# c150.net
KiCad netlist of a schematic drawn in EAGLE
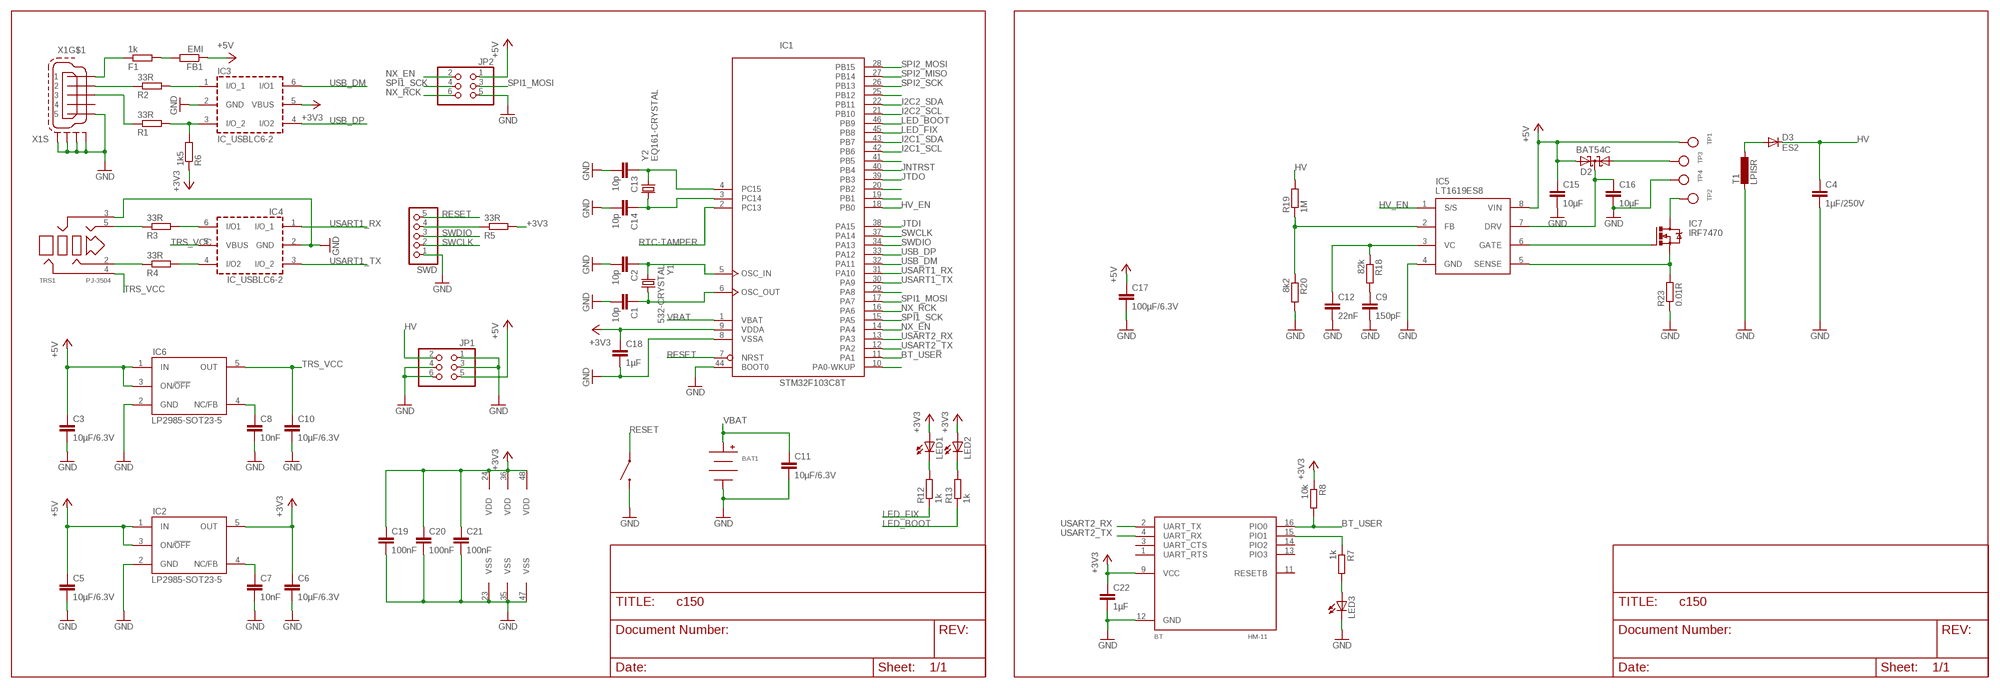
[diagram p0: schematic, sheet 1]

(export (version "E")
  (design (tool "Eeschema 10.0.6"))
  (components
    (comp (ref "BAT1")
      (value "CR1220-HOLDER")
      (footprint "eagle-import:HARWIN-CR1220")
      (libsource (lib "eagle-import") (part "CR1220-HOLDER"))
    )
    (comp (ref "BT")
      (value "HM-11")
      (footprint "eagle-import:HM-11")
      (libsource (lib "eagle-import") (part "HM-11"))
    )
    (comp (ref "C1")
      (value "10p")
      (footprint "eagle-import:C0603")
      (libsource (lib "eagle-import") (part "C-EUC0603"))
    )
    (comp (ref "C2")
      (value "10p")
      (footprint "eagle-import:C0603")
      (libsource (lib "eagle-import") (part "C-EUC0603"))
    )
    (comp (ref "C3")
      (value "10µF/6.3V")
      (footprint "eagle-import:C0603")
      (libsource (lib "eagle-import") (part "C-EUC0603"))
    )
    (comp (ref "C4")
      (value "1µF/250V")
      (footprint "eagle-import:C2220K")
      (libsource (lib "eagle-import") (part "C-EUC2220K"))
    )
    (comp (ref "C5")
      (value "10µF/6.3V")
      (footprint "eagle-import:C0603")
      (libsource (lib "eagle-import") (part "C-EUC0603"))
    )
    (comp (ref "C6")
      (value "10µF/6.3V")
      (footprint "eagle-import:C0603")
      (libsource (lib "eagle-import") (part "C-EUC0603"))
    )
    (comp (ref "C7")
      (value "10nF")
      (footprint "eagle-import:C0603")
      (libsource (lib "eagle-import") (part "C-EUC0603"))
    )
    (comp (ref "C8")
      (value "10nF")
      (footprint "eagle-import:C0603")
      (libsource (lib "eagle-import") (part "C-EUC0603"))
    )
    (comp (ref "C9")
      (value "150pF")
      (footprint "eagle-import:C0603")
      (libsource (lib "eagle-import") (part "C-EUC0603"))
    )
    (comp (ref "C10")
      (value "10µF/6.3V")
      (footprint "eagle-import:C0603")
      (libsource (lib "eagle-import") (part "C-EUC0603"))
    )
    (comp (ref "C11")
      (value "10µF/6.3V")
      (footprint "eagle-import:C0603")
      (libsource (lib "eagle-import") (part "C-EUC0603"))
    )
    (comp (ref "C12")
      (value "22nF")
      (footprint "eagle-import:C0603")
      (libsource (lib "eagle-import") (part "C-EUC0603"))
    )
    (comp (ref "C13")
      (value "10p")
      (footprint "eagle-import:C0603")
      (libsource (lib "eagle-import") (part "C-EUC0603"))
    )
    (comp (ref "C14")
      (value "10p")
      (footprint "eagle-import:C0603")
      (libsource (lib "eagle-import") (part "C-EUC0603"))
    )
    (comp (ref "C15")
      (value "10µF")
      (footprint "eagle-import:C0603")
      (libsource (lib "eagle-import") (part "C-EUC0603"))
    )
    (comp (ref "C16")
      (value "10µF")
      (footprint "eagle-import:C0603")
      (libsource (lib "eagle-import") (part "C-EUC0603"))
    )
    (comp (ref "C17")
      (value "100µF/6.3V")
      (footprint "eagle-import:C1210")
      (libsource (lib "eagle-import") (part "C-EUC1210"))
    )
    (comp (ref "C18")
      (value "1µF")
      (footprint "eagle-import:C0603")
      (libsource (lib "eagle-import") (part "C-EUC0603"))
    )
    (comp (ref "C19")
      (value "100nF")
      (footprint "eagle-import:C0603")
      (libsource (lib "eagle-import") (part "C-EUC0603"))
    )
    (comp (ref "C20")
      (value "100nF")
      (footprint "eagle-import:C0603")
      (libsource (lib "eagle-import") (part "C-EUC0603"))
    )
    (comp (ref "C21")
      (value "100nF")
      (footprint "eagle-import:C0603")
      (libsource (lib "eagle-import") (part "C-EUC0603"))
    )
    (comp (ref "C22")
      (value "1µF")
      (footprint "eagle-import:C0603")
      (libsource (lib "eagle-import") (part "C-EUC0603"))
    )
    (comp (ref "D2")
      (value "BAT54C")
      (footprint "eagle-import:SOT23")
      (libsource (lib "eagle-import") (part "BAT54C"))
    )
    (comp (ref "D3")
      (value "ES2")
      (footprint "eagle-import:DO-214AA")
      (libsource (lib "eagle-import") (part "ES2"))
    )
    (comp (ref "F1")
      (value "1k")
      (footprint "eagle-import:R0603")
      (libsource (lib "eagle-import") (part "R-EU_R0603"))
    )
    (comp (ref "FB1")
      (value "EMI")
      (footprint "eagle-import:R0603")
      (libsource (lib "eagle-import") (part "R-EU_R0603"))
    )
    (comp (ref "IC1")
      (value "STM32F103C8T")
      (footprint "eagle-import:LQFP48")
      (libsource (lib "eagle-import") (part "STM32F103CT8"))
    )
    (comp (ref "IC2")
      (value "LP2985-SOT23-5")
      (footprint "eagle-import:SOT23-5")
      (libsource (lib "eagle-import") (part "LP2985-SOT23-5"))
    )
    (comp (ref "IC3")
      (value "IC_USBLC6-2")
      (footprint "eagle-import:SOT-23-6L")
      (libsource (lib "eagle-import") (part "IC_USBLC6-2"))
    )
    (comp (ref "IC4")
      (value "IC_USBLC6-2")
      (footprint "eagle-import:SOT-23-6L")
      (libsource (lib "eagle-import") (part "IC_USBLC6-2"))
    )
    (comp (ref "IC5")
      (value "LT1619ES8")
      (footprint "eagle-import:SO8")
      (libsource (lib "eagle-import") (part "LT1619ES8"))
    )
    (comp (ref "IC6")
      (value "LP2985-SOT23-5")
      (footprint "eagle-import:SOT23-5")
      (libsource (lib "eagle-import") (part "LP2985-SOT23-5"))
    )
    (comp (ref "IC7")
      (value "IRF7470")
      (footprint "eagle-import:SO8")
      (libsource (lib "eagle-import") (part "IRF7470"))
    )
    (comp (ref "ISP")
      (value "TACT-SWITCH-40-40")
      (footprint "eagle-import:40-40")
      (libsource (lib "eagle-import") (part "TACT-SWITCH-40-40"))
    )
    (comp (ref "JP1")
      (value "PINHD-2X3_2.54-SMD")
      (footprint "eagle-import:2X03SMD")
      (libsource (lib "eagle-import") (part "PINHD-2X3_2.54-SMD"))
    )
    (comp (ref "JP2")
      (value "PINHD-2X3_2.54-SMD")
      (footprint "eagle-import:2X03SMD")
      (libsource (lib "eagle-import") (part "PINHD-2X3_2.54-SMD"))
    )
    (comp (ref "LED1")
      (value "LEDCHIP-LED0603")
      (footprint "eagle-import:CHIP-LED0603")
      (libsource (lib "eagle-import") (part "LEDCHIP-LED0603"))
    )
    (comp (ref "LED2")
      (value "LEDCHIP-LED0603")
      (footprint "eagle-import:CHIP-LED0603")
      (libsource (lib "eagle-import") (part "LEDCHIP-LED0603"))
    )
    (comp (ref "LED3")
      (value "LEDCHIP-LED0603")
      (footprint "eagle-import:CHIP-LED0603")
      (libsource (lib "eagle-import") (part "LEDCHIP-LED0603"))
    )
    (comp (ref "R1")
      (value "33R")
      (footprint "eagle-import:R0603")
      (libsource (lib "eagle-import") (part "R-EU_R0603"))
    )
    (comp (ref "R2")
      (value "33R")
      (footprint "eagle-import:R0603")
      (libsource (lib "eagle-import") (part "R-EU_R0603"))
    )
    (comp (ref "R3")
      (value "33R")
      (footprint "eagle-import:R0603")
      (libsource (lib "eagle-import") (part "R-EU_R0603"))
    )
    (comp (ref "R4")
      (value "33R")
      (footprint "eagle-import:R0603")
      (libsource (lib "eagle-import") (part "R-EU_R0603"))
    )
    (comp (ref "R5")
      (value "33R")
      (footprint "eagle-import:R0603")
      (libsource (lib "eagle-import") (part "R-EU_R0603"))
    )
    (comp (ref "R6")
      (value "1k5")
      (footprint "eagle-import:R0603")
      (libsource (lib "eagle-import") (part "R-EU_R0603"))
    )
    (comp (ref "R7")
      (value "1k")
      (footprint "eagle-import:R0603")
      (libsource (lib "eagle-import") (part "R-EU_R0603"))
    )
    (comp (ref "R8")
      (value "10k")
      (footprint "eagle-import:R0603")
      (libsource (lib "eagle-import") (part "R-EU_R0603"))
    )
    (comp (ref "R12")
      (value "1k")
      (footprint "eagle-import:R0603")
      (libsource (lib "eagle-import") (part "R-EU_R0603"))
    )
    (comp (ref "R13")
      (value "1k")
      (footprint "eagle-import:R0603")
      (libsource (lib "eagle-import") (part "R-EU_R0603"))
    )
    (comp (ref "R18")
      (value "82k")
      (footprint "eagle-import:R0603")
      (libsource (lib "eagle-import") (part "R-EU_R0603"))
    )
    (comp (ref "R19")
      (value "1M")
      (footprint "eagle-import:M1206")
      (libsource (lib "eagle-import") (part "R-EU_M1206"))
    )
    (comp (ref "R20")
      (value "8k2")
      (footprint "eagle-import:R0603")
      (libsource (lib "eagle-import") (part "R-EU_R0603"))
    )
    (comp (ref "R23")
      (value "0.01R")
      (footprint "eagle-import:R1206")
      (libsource (lib "eagle-import") (part "R-EU_R1206"))
    )
    (comp (ref "SWD")
      (value "HEADER-1X5ROUND")
      (footprint "eagle-import:1X05_ROUND")
      (libsource (lib "eagle-import") (part "HEADER-1X5ROUND"))
    )
    (comp (ref "T1")
      (value "LPISR")
      (footprint "eagle-import:PISR")
      (libsource (lib "eagle-import") (part "LPISR"))
    )
    (comp (ref "TP1")
      (value "TESTPOINTROUND2MM")
      (footprint "eagle-import:TESTPOINT_ROUND_2MM")
      (libsource (lib "eagle-import") (part "TESTPOINTROUND2MM"))
    )
    (comp (ref "TP2")
      (value "TESTPOINTROUND2MM")
      (footprint "eagle-import:TESTPOINT_ROUND_2MM")
      (libsource (lib "eagle-import") (part "TESTPOINTROUND2MM"))
    )
    (comp (ref "TP3")
      (value "TESTPOINTROUND2MM")
      (footprint "eagle-import:TESTPOINT_ROUND_2MM")
      (libsource (lib "eagle-import") (part "TESTPOINTROUND2MM"))
    )
    (comp (ref "TP4")
      (value "TESTPOINTROUND2MM")
      (footprint "eagle-import:TESTPOINT_ROUND_2MM")
      (libsource (lib "eagle-import") (part "TESTPOINTROUND2MM"))
    )
    (comp (ref "TRS1")
      (value "PJ-3504")
      (footprint "eagle-import:YD-PJ-3504")
      (libsource (lib "eagle-import") (part "PJ-3504"))
    )
    (comp (ref "X1")
      (value "MINI-USB-SCHIELD-32005-201")
      (footprint "eagle-import:32005-201")
      (libsource (lib "eagle-import") (part "MINI-USB-SCHIELD-32005-201"))
    )
    (comp (ref "Y1")
      (value "532-CRYSTAL")
      (footprint "eagle-import:2PIN50X32")
      (libsource (lib "eagle-import") (part "532-CRYSTAL"))
    )
    (comp (ref "Y2")
      (value "EQ161-CRYSTAL")
      (footprint "eagle-import:EQ161")
      (libsource (lib "eagle-import") (part "EQ161-CRYSTAL"))
    )
  )
  (nets
    (net (code "1") (name "+3V3") (class "Default")
      (node (ref "BT") (pin "9") (pinfunction "VCC_9") (pintype "bidirectional"))
      (node (ref "C18") (pin "1") (pinfunction "1_1") (pintype "passive"))
      (node (ref "C19") (pin "1") (pinfunction "1_1") (pintype "passive"))
      (node (ref "C20") (pin "1") (pinfunction "1_1") (pintype "passive"))
      (node (ref "C21") (pin "1") (pinfunction "1_1") (pintype "passive"))
      (node (ref "C22") (pin "1") (pinfunction "1_1") (pintype "passive"))
      (node (ref "C6") (pin "1") (pinfunction "1_1") (pintype "passive"))
      (node (ref "IC1") (pin "24") (pinfunction "VDD_24") (pintype "power_in"))
      (node (ref "IC1") (pin "36") (pinfunction "VDD_36") (pintype "power_in"))
      (node (ref "IC1") (pin "48") (pinfunction "VDD_48") (pintype "power_in"))
      (node (ref "IC1") (pin "9") (pinfunction "VDDA_9") (pintype "power_in"))
      (node (ref "IC2") (pin "5") (pinfunction "OUT_5") (pintype "bidirectional"))
      (node (ref "IC3") (pin "5") (pinfunction "VBUS_5") (pintype "bidirectional"))
      (node (ref "LED1") (pin "A") (pinfunction "A_A") (pintype "passive"))
      (node (ref "LED2") (pin "A") (pinfunction "A_A") (pintype "passive"))
      (node (ref "R5") (pin "2") (pinfunction "2_2") (pintype "passive"))
      (node (ref "R6") (pin "1") (pinfunction "1_1") (pintype "passive"))
      (node (ref "R8") (pin "1") (pinfunction "1_1") (pintype "passive"))
    )
    (net (code "2") (name "+5V") (class "Default")
      (node (ref "C15") (pin "1") (pinfunction "1_1") (pintype "passive"))
      (node (ref "C17") (pin "1") (pinfunction "1_1") (pintype "passive"))
      (node (ref "C3") (pin "1") (pinfunction "1_1") (pintype "passive"))
      (node (ref "C5") (pin "1") (pinfunction "1_1") (pintype "passive"))
      (node (ref "D2") (pin "2") (pinfunction "A2_2") (pintype "passive"))
      (node (ref "FB1") (pin "1") (pinfunction "1_1") (pintype "passive"))
      (node (ref "IC2") (pin "1") (pinfunction "IN_1") (pintype "bidirectional"))
      (node (ref "IC2") (pin "3") (pinfunction "ON/~{OFF}_3") (pintype "bidirectional"))
      (node (ref "IC5") (pin "8") (pinfunction "VIN_8") (pintype "bidirectional"))
      (node (ref "IC6") (pin "1") (pinfunction "IN_1") (pintype "bidirectional"))
      (node (ref "IC6") (pin "3") (pinfunction "ON/~{OFF}_3") (pintype "bidirectional"))
      (node (ref "JP1") (pin "5") (pinfunction "5_5") (pintype "passive"))
      (node (ref "JP2") (pin "1") (pinfunction "1_1") (pintype "passive"))
      (node (ref "TP1") (pin "P$1") (pinfunction "P$1_P$1") (pintype "bidirectional"))
    )
    (net (code "3") (name "/BT_USER") (class "Default")
      (node (ref "BT") (pin "16") (pinfunction "PIO0_16") (pintype "bidirectional"))
      (node (ref "IC1") (pin "11") (pinfunction "PA1_11") (pintype "bidirectional"))
      (node (ref "R8") (pin "2") (pinfunction "2_2") (pintype "passive"))
    )
    (net (code "4") (name "/HV") (class "Default")
      (node (ref "C4") (pin "1") (pinfunction "1_1") (pintype "passive"))
      (node (ref "D3") (pin "C") (pinfunction "C_C") (pintype "passive"))
      (node (ref "JP1") (pin "2") (pinfunction "2_2") (pintype "passive"))
      (node (ref "R19") (pin "2") (pinfunction "2_2") (pintype "passive"))
    )
    (net (code "5") (name "/HV_EN") (class "Default")
      (node (ref "IC1") (pin "18") (pinfunction "PB0_18") (pintype "bidirectional"))
      (node (ref "IC5") (pin "1") (pinfunction "S/S_1") (pintype "bidirectional"))
    )
    (net (code "6") (name "/I2C1_SCL") (class "Default")
      (node (ref "IC1") (pin "42") (pinfunction "PB6_42") (pintype "bidirectional"))
    )
    (net (code "7") (name "/I2C1_SDA") (class "Default")
      (node (ref "IC1") (pin "43") (pinfunction "PB7_43") (pintype "bidirectional"))
    )
    (net (code "8") (name "/I2C2_SCL") (class "Default")
      (node (ref "IC1") (pin "21") (pinfunction "PB10_21") (pintype "bidirectional"))
    )
    (net (code "9") (name "/I2C2_SDA") (class "Default")
      (node (ref "IC1") (pin "22") (pinfunction "PB11_22") (pintype "bidirectional"))
    )
    (net (code "10") (name "/JNTRST") (class "Default")
      (node (ref "IC1") (pin "40") (pinfunction "PB4_40") (pintype "bidirectional"))
    )
    (net (code "11") (name "/JTDI") (class "Default")
      (node (ref "IC1") (pin "38") (pinfunction "PA15_38") (pintype "bidirectional"))
    )
    (net (code "12") (name "/JTDO") (class "Default")
      (node (ref "IC1") (pin "39") (pinfunction "PB3_39") (pintype "bidirectional"))
    )
    (net (code "13") (name "/LED_BOOT") (class "Default")
      (node (ref "IC1") (pin "46") (pinfunction "PB9_46") (pintype "bidirectional"))
      (node (ref "R13") (pin "1") (pinfunction "1_1") (pintype "passive"))
    )
    (net (code "14") (name "/LED_FIX") (class "Default")
      (node (ref "IC1") (pin "45") (pinfunction "PB8_45") (pintype "bidirectional"))
      (node (ref "R12") (pin "1") (pinfunction "1_1") (pintype "passive"))
    )
    (net (code "15") (name "/NX_EN") (class "Default")
      (node (ref "IC1") (pin "14") (pinfunction "PA4_14") (pintype "bidirectional"))
      (node (ref "JP2") (pin "2") (pinfunction "2_2") (pintype "passive"))
    )
    (net (code "16") (name "/NX_RCK") (class "Default")
      (node (ref "IC1") (pin "16") (pinfunction "PA6_16") (pintype "bidirectional"))
      (node (ref "JP2") (pin "6") (pinfunction "6_6") (pintype "passive"))
    )
    (net (code "17") (name "/RESET") (class "Default")
      (node (ref "IC1") (pin "7") (pinfunction "NRST_7") (pintype "bidirectional"))
      (node (ref "ISP") (pin "3") (pinfunction "P$2_3") (pintype "bidirectional"))
      (node (ref "ISP") (pin "4") (pinfunction "P$2_4") (pintype "bidirectional"))
      (node (ref "SWD") (pin "5") (pinfunction "5_5") (pintype "passive"))
    )
    (net (code "18") (name "/RTC-TAMPER") (class "Default")
      (node (ref "IC1") (pin "2") (pinfunction "PC13_2") (pintype "bidirectional"))
    )
    (net (code "19") (name "/SPI1_MOSI") (class "Default")
      (node (ref "IC1") (pin "17") (pinfunction "PA7_17") (pintype "bidirectional"))
      (node (ref "JP2") (pin "3") (pinfunction "3_3") (pintype "passive"))
    )
    (net (code "20") (name "/SPI1_SCK") (class "Default")
      (node (ref "IC1") (pin "15") (pinfunction "PA5_15") (pintype "bidirectional"))
      (node (ref "JP2") (pin "4") (pinfunction "4_4") (pintype "passive"))
    )
    (net (code "21") (name "/SPI2_MISO") (class "Default")
      (node (ref "IC1") (pin "27") (pinfunction "PB14_27") (pintype "bidirectional"))
    )
    (net (code "22") (name "/SPI2_MOSI") (class "Default")
      (node (ref "IC1") (pin "28") (pinfunction "PB15_28") (pintype "bidirectional"))
    )
    (net (code "23") (name "/SPI2_SCK") (class "Default")
      (node (ref "IC1") (pin "26") (pinfunction "PB13_26") (pintype "bidirectional"))
    )
    (net (code "24") (name "/SWCLK") (class "Default")
      (node (ref "IC1") (pin "37") (pinfunction "PA14_37") (pintype "bidirectional"))
      (node (ref "SWD") (pin "2") (pinfunction "2_2") (pintype "passive"))
    )
    (net (code "25") (name "/SWDIO") (class "Default")
      (node (ref "IC1") (pin "34") (pinfunction "PA13_34") (pintype "bidirectional"))
      (node (ref "SWD") (pin "3") (pinfunction "3_3") (pintype "passive"))
    )
    (net (code "26") (name "/TRS_VCC") (class "Default")
      (node (ref "C10") (pin "1") (pinfunction "1_1") (pintype "passive"))
      (node (ref "IC4") (pin "5") (pinfunction "VBUS_5") (pintype "bidirectional"))
      (node (ref "IC6") (pin "5") (pinfunction "OUT_5") (pintype "bidirectional"))
      (node (ref "TRS1") (pin "4") (pinfunction "4_4") (pintype "bidirectional"))
    )
    (net (code "27") (name "/USART1_RX") (class "Default")
      (node (ref "IC1") (pin "31") (pinfunction "PA10_31") (pintype "bidirectional"))
      (node (ref "IC4") (pin "1") (pinfunction "I/O_1_1") (pintype "bidirectional"))
    )
    (net (code "28") (name "/USART1_TX") (class "Default")
      (node (ref "IC1") (pin "30") (pinfunction "PA9_30") (pintype "bidirectional"))
      (node (ref "IC4") (pin "3") (pinfunction "I/O_2_3") (pintype "bidirectional"))
    )
    (net (code "29") (name "/USART2_RX") (class "Default")
      (node (ref "BT") (pin "2") (pinfunction "UART_TX_2") (pintype "bidirectional"))
      (node (ref "IC1") (pin "13") (pinfunction "PA3_13") (pintype "bidirectional"))
    )
    (net (code "30") (name "/USART2_TX") (class "Default")
      (node (ref "BT") (pin "4") (pinfunction "UART_RX_4") (pintype "bidirectional"))
      (node (ref "IC1") (pin "12") (pinfunction "PA2_12") (pintype "bidirectional"))
    )
    (net (code "31") (name "/USB_DM") (class "Default")
      (node (ref "IC1") (pin "32") (pinfunction "PA11_32") (pintype "bidirectional"))
      (node (ref "IC3") (pin "6") (pinfunction "I/O1_6") (pintype "bidirectional"))
    )
    (net (code "32") (name "/USB_DP") (class "Default")
      (node (ref "IC1") (pin "33") (pinfunction "PA12_33") (pintype "bidirectional"))
      (node (ref "IC3") (pin "4") (pinfunction "I/O2_4") (pintype "bidirectional"))
    )
    (net (code "33") (name "/VBAT") (class "Default")
      (node (ref "BAT1") (pin "POS") (pinfunction "POS_POS") (pintype "bidirectional"))
      (node (ref "C11") (pin "1") (pinfunction "1_1") (pintype "passive"))
      (node (ref "IC1") (pin "1") (pinfunction "VBAT_1") (pintype "power_in"))
    )
    (net (code "34") (name "GND") (class "Default")
      (node (ref "BAT1") (pin "NEG") (pinfunction "NEG_NEG") (pintype "bidirectional"))
      (node (ref "BT") (pin "12") (pinfunction "GND_12") (pintype "bidirectional"))
      (node (ref "C1") (pin "2") (pinfunction "2_2") (pintype "passive"))
      (node (ref "C10") (pin "2") (pinfunction "2_2") (pintype "passive"))
      (node (ref "C11") (pin "2") (pinfunction "2_2") (pintype "passive"))
      (node (ref "C12") (pin "2") (pinfunction "2_2") (pintype "passive"))
      (node (ref "C13") (pin "2") (pinfunction "2_2") (pintype "passive"))
      (node (ref "C14") (pin "2") (pinfunction "2_2") (pintype "passive"))
      (node (ref "C15") (pin "2") (pinfunction "2_2") (pintype "passive"))
      (node (ref "C16") (pin "2") (pinfunction "2_2") (pintype "passive"))
      (node (ref "C17") (pin "2") (pinfunction "2_2") (pintype "passive"))
      (node (ref "C18") (pin "2") (pinfunction "2_2") (pintype "passive"))
      (node (ref "C19") (pin "2") (pinfunction "2_2") (pintype "passive"))
      (node (ref "C2") (pin "2") (pinfunction "2_2") (pintype "passive"))
      (node (ref "C20") (pin "2") (pinfunction "2_2") (pintype "passive"))
      (node (ref "C21") (pin "2") (pinfunction "2_2") (pintype "passive"))
      (node (ref "C22") (pin "2") (pinfunction "2_2") (pintype "passive"))
      (node (ref "C3") (pin "2") (pinfunction "2_2") (pintype "passive"))
      (node (ref "C4") (pin "2") (pinfunction "2_2") (pintype "passive"))
      (node (ref "C5") (pin "2") (pinfunction "2_2") (pintype "passive"))
      (node (ref "C6") (pin "2") (pinfunction "2_2") (pintype "passive"))
      (node (ref "C7") (pin "2") (pinfunction "2_2") (pintype "passive"))
      (node (ref "C8") (pin "2") (pinfunction "2_2") (pintype "passive"))
      (node (ref "C9") (pin "2") (pinfunction "2_2") (pintype "passive"))
      (node (ref "IC1") (pin "23") (pinfunction "VSS_23") (pintype "power_in"))
      (node (ref "IC1") (pin "35") (pinfunction "VSS_35") (pintype "power_in"))
      (node (ref "IC1") (pin "44") (pinfunction "BOOT0_44") (pintype "input"))
      (node (ref "IC1") (pin "47") (pinfunction "VSS_47") (pintype "power_in"))
      (node (ref "IC1") (pin "8") (pinfunction "VSSA_8") (pintype "power_in"))
      (node (ref "IC2") (pin "2") (pinfunction "GND_2") (pintype "bidirectional"))
      (node (ref "IC3") (pin "2") (pinfunction "GND_2") (pintype "bidirectional"))
      (node (ref "IC4") (pin "2") (pinfunction "GND_2") (pintype "bidirectional"))
      (node (ref "IC5") (pin "4") (pinfunction "GND_4") (pintype "bidirectional"))
      (node (ref "IC6") (pin "2") (pinfunction "GND_2") (pintype "bidirectional"))
      (node (ref "ISP") (pin "1") (pinfunction "P$1_1") (pintype "bidirectional"))
      (node (ref "ISP") (pin "2") (pinfunction "P$1_2") (pintype "bidirectional"))
      (node (ref "JP1") (pin "1") (pinfunction "1_1") (pintype "passive"))
      (node (ref "JP1") (pin "3") (pinfunction "3_3") (pintype "passive"))
      (node (ref "JP1") (pin "4") (pinfunction "4_4") (pintype "passive"))
      (node (ref "JP1") (pin "6") (pinfunction "6_6") (pintype "passive"))
      (node (ref "JP2") (pin "5") (pinfunction "5_5") (pintype "passive"))
      (node (ref "LED3") (pin "C") (pinfunction "C_C") (pintype "passive"))
      (node (ref "R20") (pin "2") (pinfunction "2_2") (pintype "passive"))
      (node (ref "R23") (pin "1") (pinfunction "1_1") (pintype "passive"))
      (node (ref "SWD") (pin "1") (pinfunction "1_1") (pintype "passive"))
      (node (ref "T1") (pin "P$2") (pinfunction "2_P$2") (pintype "passive"))
      (node (ref "TP4") (pin "P$1") (pinfunction "P$1_P$1") (pintype "bidirectional"))
      (node (ref "TRS1") (pin "3") (pinfunction "3_3") (pintype "bidirectional"))
      (node (ref "X1") (pin "5") (pinfunction "5_5") (pintype "passive"))
      (node (ref "X1") (pin "M1") (pinfunction "S1_M1") (pintype "passive"))
      (node (ref "X1") (pin "M2") (pinfunction "S2_M2") (pintype "passive"))
      (node (ref "X1") (pin "M3") (pinfunction "S3_M3") (pintype "passive"))
      (node (ref "X1") (pin "M4") (pinfunction "S4_M4") (pintype "passive"))
    )
    (net (code "35") (name "Net-(BT-PIO1)") (class "Default")
      (node (ref "BT") (pin "15") (pinfunction "PIO1_15") (pintype "bidirectional"))
      (node (ref "R7") (pin "1") (pinfunction "1_1") (pintype "passive"))
    )
    (net (code "36") (name "Net-(C9-Pad1)") (class "Default")
      (node (ref "C9") (pin "1") (pinfunction "1_1") (pintype "passive"))
      (node (ref "R18") (pin "2") (pinfunction "2_2") (pintype "passive"))
    )
    (net (code "37") (name "Net-(D2-A1)") (class "Default")
      (node (ref "D2") (pin "1") (pinfunction "A1_1") (pintype "passive"))
      (node (ref "TP3") (pin "P$1") (pinfunction "P$1_P$1") (pintype "bidirectional"))
    )
    (net (code "38") (name "Net-(D2-CC)") (class "Default")
      (node (ref "C16") (pin "1") (pinfunction "1_1") (pintype "passive"))
      (node (ref "D2") (pin "3") (pinfunction "CC_3") (pintype "passive"))
      (node (ref "IC5") (pin "7") (pinfunction "DRV_7") (pintype "bidirectional"))
    )
    (net (code "39") (name "Net-(F1-Pad1)") (class "Default")
      (node (ref "F1") (pin "1") (pinfunction "1_1") (pintype "passive"))
      (node (ref "X1") (pin "1") (pinfunction "1_1") (pintype "passive"))
    )
    (net (code "40") (name "Net-(F1-Pad2)") (class "Default")
      (node (ref "F1") (pin "2") (pinfunction "2_2") (pintype "passive"))
      (node (ref "FB1") (pin "2") (pinfunction "2_2") (pintype "passive"))
    )
    (net (code "41") (name "Net-(IC1A-OSC_IN)") (class "Default")
      (node (ref "C2") (pin "1") (pinfunction "1_1") (pintype "passive"))
      (node (ref "IC1") (pin "5") (pinfunction "OSC_IN_5") (pintype "bidirectional"))
      (node (ref "Y1") (pin "P$2") (pinfunction "2_P$2") (pintype "passive"))
    )
    (net (code "42") (name "Net-(IC1A-OSC_OUT)") (class "Default")
      (node (ref "C1") (pin "1") (pinfunction "1_1") (pintype "passive"))
      (node (ref "IC1") (pin "6") (pinfunction "OSC_OUT_6") (pintype "bidirectional"))
      (node (ref "Y1") (pin "P$1") (pinfunction "1_P$1") (pintype "passive"))
    )
    (net (code "43") (name "Net-(IC1A-PC14)") (class "Default")
      (node (ref "C14") (pin "1") (pinfunction "1_1") (pintype "passive"))
      (node (ref "IC1") (pin "3") (pinfunction "PC14_3") (pintype "bidirectional"))
      (node (ref "Y2") (pin "P$2") (pinfunction "2_P$2") (pintype "passive"))
    )
    (net (code "44") (name "Net-(IC1A-PC15)") (class "Default")
      (node (ref "C13") (pin "1") (pinfunction "1_1") (pintype "passive"))
      (node (ref "IC1") (pin "4") (pinfunction "PC15_4") (pintype "bidirectional"))
      (node (ref "Y2") (pin "P$1") (pinfunction "1_P$1") (pintype "passive"))
    )
    (net (code "45") (name "Net-(IC2-NC{slash}FB)") (class "Default")
      (node (ref "C7") (pin "1") (pinfunction "1_1") (pintype "passive"))
      (node (ref "IC2") (pin "4") (pinfunction "NC/FB_4") (pintype "bidirectional"))
    )
    (net (code "46") (name "Net-(IC3-I{slash}O_1)") (class "Default")
      (node (ref "IC3") (pin "1") (pinfunction "I/O_1_1") (pintype "bidirectional"))
      (node (ref "R2") (pin "2") (pinfunction "2_2") (pintype "passive"))
    )
    (net (code "47") (name "Net-(IC3-I{slash}O_2)") (class "Default")
      (node (ref "IC3") (pin "3") (pinfunction "I/O_2_3") (pintype "bidirectional"))
      (node (ref "R1") (pin "2") (pinfunction "2_2") (pintype "passive"))
      (node (ref "R6") (pin "2") (pinfunction "2_2") (pintype "passive"))
    )
    (net (code "48") (name "Net-(IC4-I{slash}O1)") (class "Default")
      (node (ref "IC4") (pin "6") (pinfunction "I/O1_6") (pintype "bidirectional"))
      (node (ref "R3") (pin "2") (pinfunction "2_2") (pintype "passive"))
    )
    (net (code "49") (name "Net-(IC4-I{slash}O2)") (class "Default")
      (node (ref "IC4") (pin "4") (pinfunction "I/O2_4") (pintype "bidirectional"))
      (node (ref "R4") (pin "2") (pinfunction "2_2") (pintype "passive"))
    )
    (net (code "50") (name "Net-(IC5-FB)") (class "Default")
      (node (ref "IC5") (pin "2") (pinfunction "FB_2") (pintype "bidirectional"))
      (node (ref "R19") (pin "1") (pinfunction "1_1") (pintype "passive"))
      (node (ref "R20") (pin "1") (pinfunction "1_1") (pintype "passive"))
    )
    (net (code "51") (name "Net-(IC5-GATE)") (class "Default")
      (node (ref "IC5") (pin "6") (pinfunction "GATE_6") (pintype "bidirectional"))
      (node (ref "IC7") (pin "4") (pinfunction "G_4") (pintype "passive"))
    )
    (net (code "52") (name "Net-(IC5-SENSE)") (class "Default")
      (node (ref "IC5") (pin "5") (pinfunction "SENSE_5") (pintype "bidirectional"))
      (node (ref "IC7") (pin "1") (pinfunction "S_1") (pintype "passive"))
      (node (ref "IC7") (pin "2") (pinfunction "S_2") (pintype "passive"))
      (node (ref "IC7") (pin "3") (pinfunction "S_3") (pintype "passive"))
      (node (ref "R23") (pin "2") (pinfunction "2_2") (pintype "passive"))
    )
    (net (code "53") (name "Net-(IC5-VC)") (class "Default")
      (node (ref "C12") (pin "1") (pinfunction "1_1") (pintype "passive"))
      (node (ref "IC5") (pin "3") (pinfunction "VC_3") (pintype "bidirectional"))
      (node (ref "R18") (pin "1") (pinfunction "1_1") (pintype "passive"))
    )
    (net (code "54") (name "Net-(IC6-NC{slash}FB)") (class "Default")
      (node (ref "C8") (pin "1") (pinfunction "1_1") (pintype "passive"))
      (node (ref "IC6") (pin "4") (pinfunction "NC/FB_4") (pintype "bidirectional"))
    )
    (net (code "55") (name "Net-(IC7-D-Pad5)") (class "Default")
      (node (ref "IC7") (pin "5") (pinfunction "D_5") (pintype "passive"))
      (node (ref "IC7") (pin "6") (pinfunction "D_6") (pintype "passive"))
      (node (ref "IC7") (pin "7") (pinfunction "D_7") (pintype "passive"))
      (node (ref "IC7") (pin "8") (pinfunction "D_8") (pintype "passive"))
      (node (ref "TP2") (pin "P$1") (pinfunction "P$1_P$1") (pintype "bidirectional"))
    )
    (net (code "56") (name "Net-(LED1-PadC)") (class "Default")
      (node (ref "LED1") (pin "C") (pinfunction "C_C") (pintype "passive"))
      (node (ref "R12") (pin "2") (pinfunction "2_2") (pintype "passive"))
    )
    (net (code "57") (name "Net-(LED2-PadC)") (class "Default")
      (node (ref "LED2") (pin "C") (pinfunction "C_C") (pintype "passive"))
      (node (ref "R13") (pin "2") (pinfunction "2_2") (pintype "passive"))
    )
    (net (code "58") (name "Net-(LED3-PadA)") (class "Default")
      (node (ref "LED3") (pin "A") (pinfunction "A_A") (pintype "passive"))
      (node (ref "R7") (pin "2") (pinfunction "2_2") (pintype "passive"))
    )
    (net (code "59") (name "Net-(R1-Pad1)") (class "Default")
      (node (ref "R1") (pin "1") (pinfunction "1_1") (pintype "passive"))
      (node (ref "X1") (pin "3") (pinfunction "3_3") (pintype "passive"))
    )
    (net (code "60") (name "Net-(R2-Pad1)") (class "Default")
      (node (ref "R2") (pin "1") (pinfunction "1_1") (pintype "passive"))
      (node (ref "X1") (pin "2") (pinfunction "2_2") (pintype "passive"))
    )
    (net (code "61") (name "Net-(R3-Pad1)") (class "Default")
      (node (ref "R3") (pin "1") (pinfunction "1_1") (pintype "passive"))
      (node (ref "TRS1") (pin "5") (pinfunction "5_5") (pintype "bidirectional"))
    )
    (net (code "62") (name "Net-(R4-Pad1)") (class "Default")
      (node (ref "R4") (pin "1") (pinfunction "1_1") (pintype "passive"))
      (node (ref "TRS1") (pin "2") (pinfunction "2_2") (pintype "bidirectional"))
    )
    (net (code "63") (name "Net-(R5-Pad1)") (class "Default")
      (node (ref "R5") (pin "1") (pinfunction "1_1") (pintype "passive"))
      (node (ref "SWD") (pin "4") (pinfunction "4_4") (pintype "passive"))
    )
    (net (code "64") (name "Net-(T1-1)") (class "Default")
      (node (ref "D3") (pin "A") (pinfunction "A_A") (pintype "passive"))
      (node (ref "T1") (pin "P$1") (pinfunction "1_P$1") (pintype "passive"))
    )
    (net (code "65") (name "unconnected-(BT-PIO2-Pad14)") (class "Default")
      (node (ref "BT") (pin "14") (pinfunction "PIO2_14") (pintype "bidirectional"))
    )
    (net (code "66") (name "unconnected-(BT-PIO3-Pad13)") (class "Default")
      (node (ref "BT") (pin "13") (pinfunction "PIO3_13") (pintype "bidirectional"))
    )
    (net (code "67") (name "unconnected-(BT-RESETB-Pad11)") (class "Default")
      (node (ref "BT") (pin "11") (pinfunction "RESETB_11") (pintype "bidirectional"))
    )
    (net (code "68") (name "unconnected-(BT-UART_CTS-Pad3)") (class "Default")
      (node (ref "BT") (pin "3") (pinfunction "UART_CTS_3") (pintype "bidirectional"))
    )
    (net (code "69") (name "unconnected-(BT-UART_RTS-Pad1)") (class "Default")
      (node (ref "BT") (pin "1") (pinfunction "UART_RTS_1") (pintype "bidirectional"))
    )
    (net (code "70") (name "unconnected-(IC1A-PA0-WKUP-Pad10)") (class "Default")
      (node (ref "IC1") (pin "10") (pinfunction "PA0-WKUP_10") (pintype "bidirectional"))
    )
    (net (code "71") (name "unconnected-(IC1A-PA8-Pad29)") (class "Default")
      (node (ref "IC1") (pin "29") (pinfunction "PA8_29") (pintype "bidirectional"))
    )
    (net (code "72") (name "unconnected-(IC1A-PB1-Pad19)") (class "Default")
      (node (ref "IC1") (pin "19") (pinfunction "PB1_19") (pintype "bidirectional"))
    )
    (net (code "73") (name "unconnected-(IC1A-PB2-Pad20)") (class "Default")
      (node (ref "IC1") (pin "20") (pinfunction "PB2_20") (pintype "bidirectional"))
    )
    (net (code "74") (name "unconnected-(IC1A-PB5-Pad41)") (class "Default")
      (node (ref "IC1") (pin "41") (pinfunction "PB5_41") (pintype "bidirectional"))
    )
    (net (code "75") (name "unconnected-(IC1A-PB12-Pad25)") (class "Default")
      (node (ref "IC1") (pin "25") (pinfunction "PB12_25") (pintype "bidirectional"))
    )
    (net (code "76") (name "unconnected-(X1-Pad4)") (class "Default")
      (node (ref "X1") (pin "4") (pinfunction "4_4") (pintype "passive"))
    )
  )
)
